# Schematic.net
KiCad netlist of a schematic drawn in EAGLE
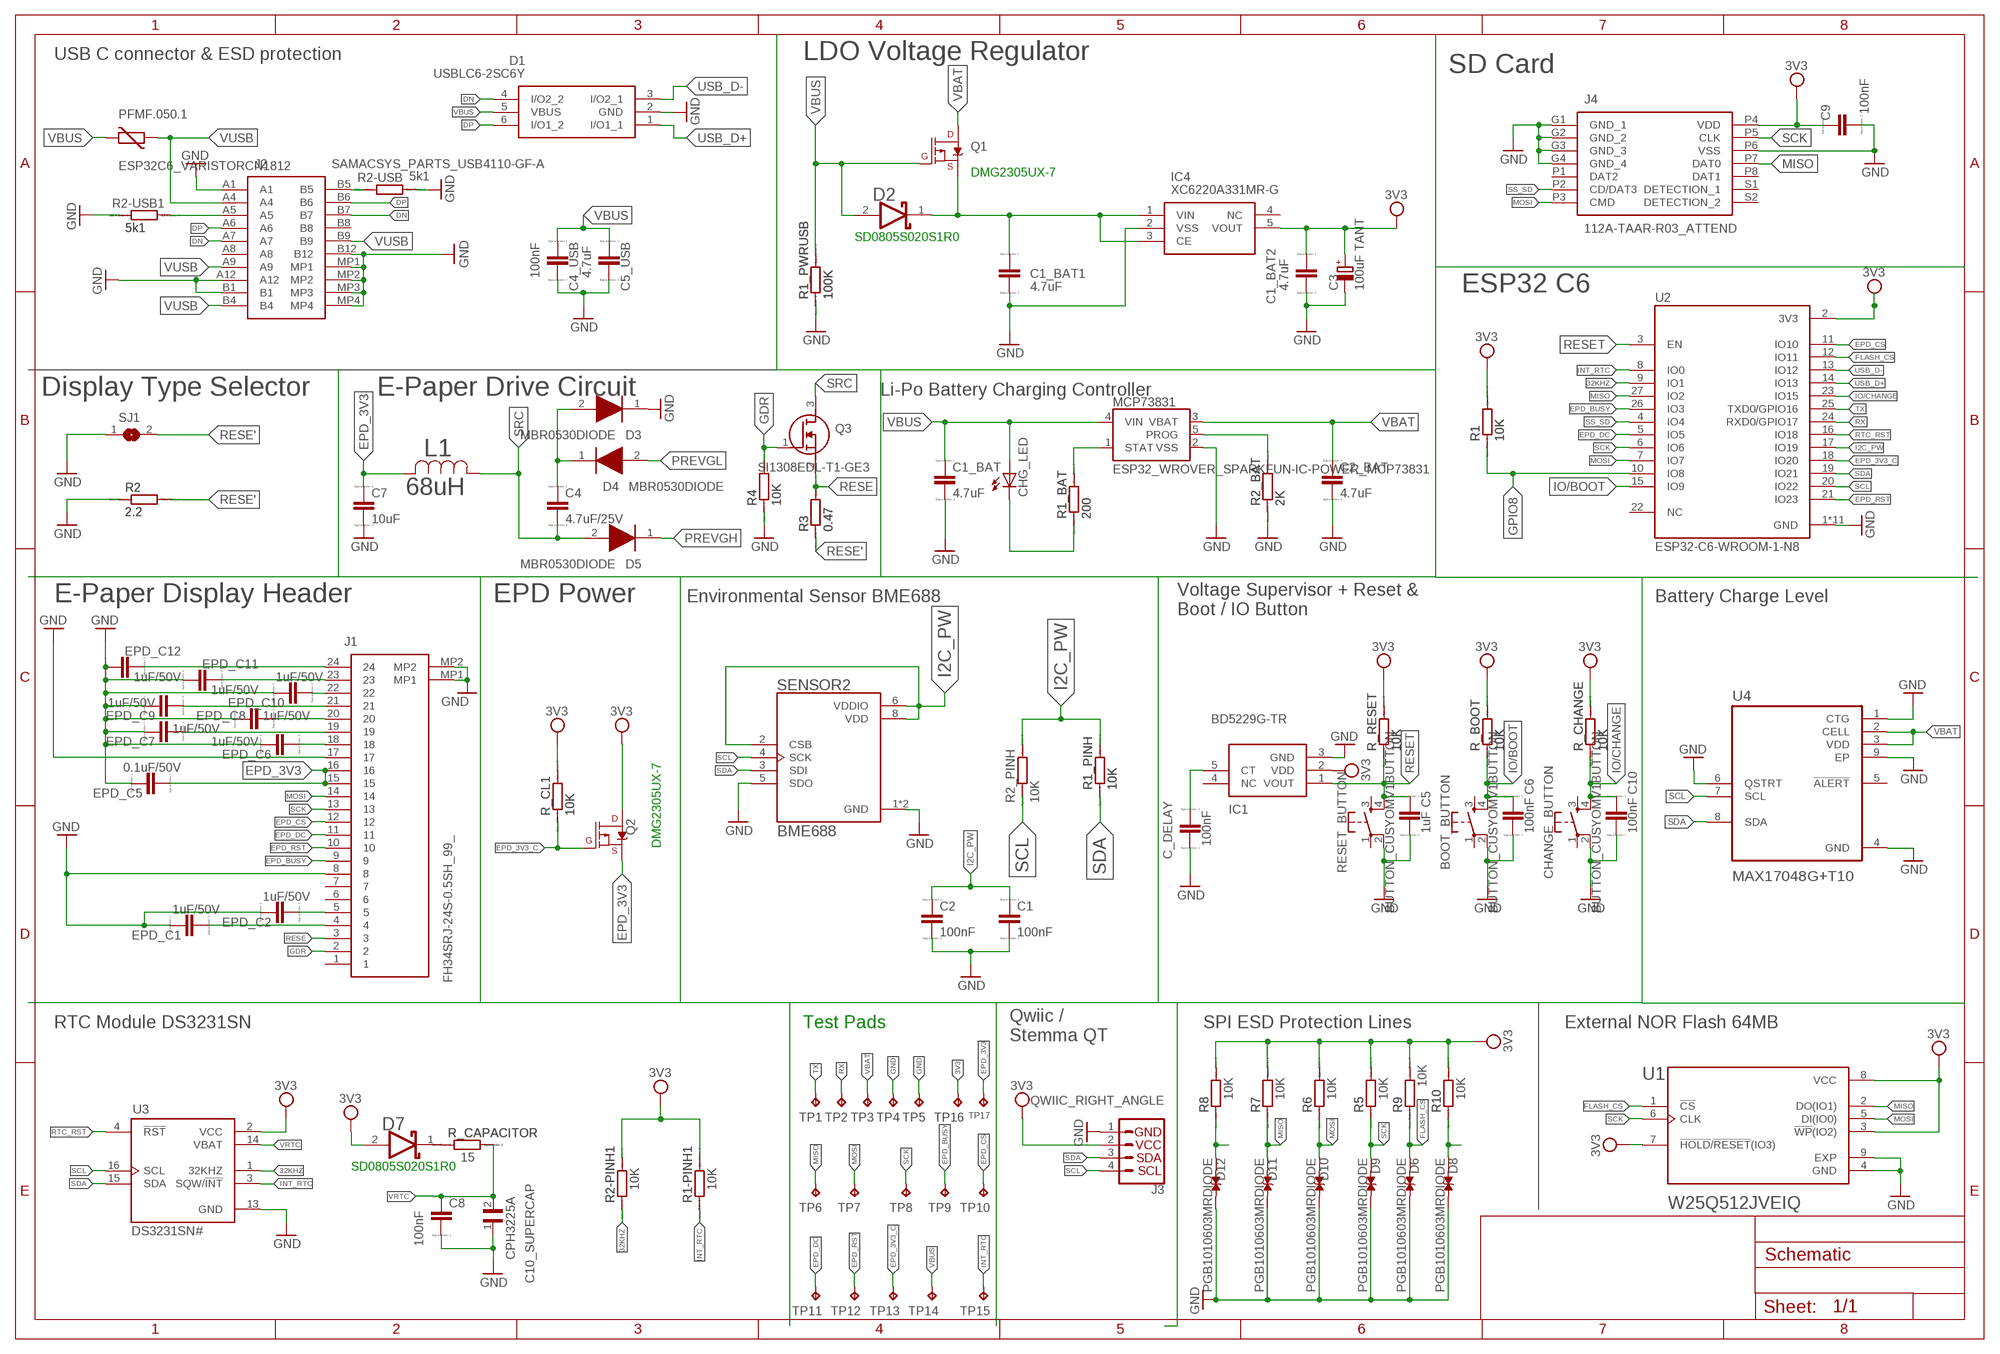
[diagram p0: schematic, sheet 1]

(export (version "E")
  (design (tool "Eeschema 10.0.6"))
  (components
    (comp (ref "BOOT_BUTTON")
      (value "BUTTON_CUSYOMV1BUTTON")
      (footprint "eagle-import:MYBUTTON")
      (libsource (lib "eagle-import") (part "BUTTON_CUSYOMV1BUTTON"))
    )
    (comp (ref "C1")
      (value "100nF")
      (footprint "eagle-import:EAGLE-LTSPICE_C0402")
      (libsource (lib "eagle-import") (part "ESP32_WROVER_EAGLE-LTSPICE_CC0402"))
    )
    (comp (ref "C1_BAT")
      (value "4.7uF")
      (footprint "eagle-import:EAGLE-LTSPICE_C0402")
      (libsource (lib "eagle-import") (part "ESP32_WROVER_EAGLE-LTSPICE_CC0402"))
    )
    (comp (ref "C1_BAT1")
      (value "4.7uF")
      (footprint "eagle-import:EAGLE-LTSPICE_C0402")
      (libsource (lib "eagle-import") (part "ESP32_WROVER_EAGLE-LTSPICE_CC0402"))
    )
    (comp (ref "C1_BAT2")
      (value "4.7uF")
      (footprint "eagle-import:EAGLE-LTSPICE_C0402")
      (libsource (lib "eagle-import") (part "ESP32_WROVER_EAGLE-LTSPICE_CC0402"))
    )
    (comp (ref "C2")
      (value "100nF")
      (footprint "eagle-import:EAGLE-LTSPICE_C0402")
      (libsource (lib "eagle-import") (part "ESP32_WROVER_EAGLE-LTSPICE_CC0402"))
    )
    (comp (ref "C2_BAT")
      (value "4.7uF")
      (footprint "eagle-import:EAGLE-LTSPICE_C0402")
      (libsource (lib "eagle-import") (part "ESP32_WROVER_EAGLE-LTSPICE_CC0402"))
    )
    (comp (ref "C3")
      (value "100uF TANT")
      (footprint "eagle-import:RCL_CT3528")
      (libsource (lib "eagle-import") (part "RCL_CPOL-EUCT3528"))
    )
    (comp (ref "C4")
      (value "4.7uF/25V")
      (footprint "eagle-import:EAGLE-LTSPICE_C0402")
      (libsource (lib "eagle-import") (part "ESP32_WROVER_EAGLE-LTSPICE_CC0402"))
    )
    (comp (ref "C4_USB")
      (value "100nF")
      (footprint "eagle-import:EAGLE-LTSPICE_C0402")
      (libsource (lib "eagle-import") (part "ESP32_WROVER_EAGLE-LTSPICE_CC0402"))
    )
    (comp (ref "C5")
      (value "1uF")
      (footprint "eagle-import:EAGLE-LTSPICE_C0402")
      (libsource (lib "eagle-import") (part "ESP32_WROVER_EAGLE-LTSPICE_CC0402"))
    )
    (comp (ref "C5_USB")
      (value "4.7uF")
      (footprint "eagle-import:EAGLE-LTSPICE_C0402")
      (libsource (lib "eagle-import") (part "ESP32_WROVER_EAGLE-LTSPICE_CC0402"))
    )
    (comp (ref "C6")
      (value "100nF")
      (footprint "eagle-import:EAGLE-LTSPICE_C0402")
      (libsource (lib "eagle-import") (part "ESP32_WROVER_EAGLE-LTSPICE_CC0402"))
    )
    (comp (ref "C7")
      (value "10uF")
      (footprint "eagle-import:EAGLE-LTSPICE_C0402")
      (libsource (lib "eagle-import") (part "ESP32_WROVER_EAGLE-LTSPICE_CC0402"))
    )
    (comp (ref "C8")
      (value "100nF")
      (footprint "eagle-import:EAGLE-LTSPICE_C0402")
      (libsource (lib "eagle-import") (part "ESP32_WROVER_EAGLE-LTSPICE_CC0402"))
    )
    (comp (ref "C9")
      (value "100nF")
      (footprint "eagle-import:EAGLE-LTSPICE_C0402")
      (libsource (lib "eagle-import") (part "ESP32_WROVER_EAGLE-LTSPICE_CC0402"))
    )
    (comp (ref "C10")
      (value "100nF")
      (footprint "eagle-import:EAGLE-LTSPICE_C0402")
      (libsource (lib "eagle-import") (part "ESP32_WROVER_EAGLE-LTSPICE_CC0402"))
    )
    (comp (ref "C10_SUPERCAP")
      (value "CPH3225A")
      (footprint "eagle-import:CAPCP3225X100N")
      (fields (field (name "MF") "Seiko Instruments"))
      (libsource (lib "eagle-import") (part "CPH3225A"))
    )
    (comp (ref "CHANGE_BUTTON")
      (value "BUTTON_CUSYOMV1BUTTON")
      (footprint "eagle-import:MYBUTTON")
      (libsource (lib "eagle-import") (part "BUTTON_CUSYOMV1BUTTON"))
    )
    (comp (ref "CHG_LED")
      (value "ADAFRUIT_LEDCHIP-LED0603")
      (footprint "eagle-import:ADAFRUIT_CHIP-LED0603")
      (libsource (lib "eagle-import") (part "ADAFRUIT_LEDCHIP-LED0603"))
    )
    (comp (ref "C_DELAY")
      (value "100nF")
      (footprint "eagle-import:EAGLE-LTSPICE_C0402")
      (libsource (lib "eagle-import") (part "ESP32_WROVER_EAGLE-LTSPICE_CC0402"))
    )
    (comp (ref "D1")
      (value "USBLC6-2SC6Y")
      (footprint "eagle-import:SOT95P280X145-6N")
      (fields (field (name "MF") "STMicroelectronics"))
      (libsource (lib "eagle-import") (part "USBLC6-2SC6Y"))
    )
    (comp (ref "D2")
      (value "SD0805S020S1R0")
      (footprint "eagle-import:ESP32_WROVER_AVX---SD0805S020S1R0_AVX_SD0805S020S1R0_0")
      (fields
        (field (name "DIGIKEY_PART_NUMBER") "478-7800-1-ND")
        (field (name "MF") "AVX")
        (field (name "MOUSER_PART_NUMBER") "581-SD0805S020S1R0")
      )
      (libsource (lib "eagle-import") (part "ESP32_WROVER_AVX---SD0805S020S1R0_AVX_SD0805S020S1R0_0_0AVX_SD0805S020S1R0_0_0"))
    )
    (comp (ref "D3")
      (value "MBR0530DIODE")
      (footprint "eagle-import:SOD3716X135N")
      (libsource (lib "eagle-import") (part "MBR0530DIODE"))
    )
    (comp (ref "D4")
      (value "MBR0530DIODE")
      (footprint "eagle-import:SOD3716X135N")
      (libsource (lib "eagle-import") (part "MBR0530DIODE"))
    )
    (comp (ref "D5")
      (value "MBR0530DIODE")
      (footprint "eagle-import:SOD3716X135N")
      (libsource (lib "eagle-import") (part "MBR0530DIODE"))
    )
    (comp (ref "D6")
      (value "PGB1010603MRDIODE")
      (footprint "eagle-import:DIOC1608X36N")
      (libsource (lib "eagle-import") (part "PGB1010603MRDIODE"))
    )
    (comp (ref "D7")
      (value "SD0805S020S1R0")
      (footprint "eagle-import:ESP32_WROVER_AVX---SD0805S020S1R0_AVX_SD0805S020S1R0_0")
      (fields
        (field (name "DIGIKEY_PART_NUMBER") "478-7800-1-ND")
        (field (name "MF") "AVX")
        (field (name "MOUSER_PART_NUMBER") "581-SD0805S020S1R0")
      )
      (libsource (lib "eagle-import") (part "ESP32_WROVER_AVX---SD0805S020S1R0_AVX_SD0805S020S1R0_0_0AVX_SD0805S020S1R0_0_0"))
    )
    (comp (ref "D8")
      (value "PGB1010603MRDIODE")
      (footprint "eagle-import:DIOC1608X36N")
      (libsource (lib "eagle-import") (part "PGB1010603MRDIODE"))
    )
    (comp (ref "D9")
      (value "PGB1010603MRDIODE")
      (footprint "eagle-import:DIOC1608X36N")
      (libsource (lib "eagle-import") (part "PGB1010603MRDIODE"))
    )
    (comp (ref "D10")
      (value "PGB1010603MRDIODE")
      (footprint "eagle-import:DIOC1608X36N")
      (libsource (lib "eagle-import") (part "PGB1010603MRDIODE"))
    )
    (comp (ref "D11")
      (value "PGB1010603MRDIODE")
      (footprint "eagle-import:DIOC1608X36N")
      (libsource (lib "eagle-import") (part "PGB1010603MRDIODE"))
    )
    (comp (ref "D12")
      (value "PGB1010603MRDIODE")
      (footprint "eagle-import:DIOC1608X36N")
      (libsource (lib "eagle-import") (part "PGB1010603MRDIODE"))
    )
    (comp (ref "EPD_C1")
      (value "1uF/50V")
      (footprint "eagle-import:EAGLE-LTSPICE_C0402")
      (libsource (lib "eagle-import") (part "ESP32_WROVER_EAGLE-LTSPICE_CC0402"))
    )
    (comp (ref "EPD_C2")
      (value "1uF/50V")
      (footprint "eagle-import:EAGLE-LTSPICE_C0402")
      (libsource (lib "eagle-import") (part "ESP32_WROVER_EAGLE-LTSPICE_CC0402"))
    )
    (comp (ref "EPD_C5")
      (value "0.1uF/50V")
      (footprint "eagle-import:EAGLE-LTSPICE_C0402")
      (libsource (lib "eagle-import") (part "ESP32_WROVER_EAGLE-LTSPICE_CC0402"))
    )
    (comp (ref "EPD_C6")
      (value "1uF/50V")
      (footprint "eagle-import:EAGLE-LTSPICE_C0402")
      (libsource (lib "eagle-import") (part "ESP32_WROVER_EAGLE-LTSPICE_CC0402"))
    )
    (comp (ref "EPD_C7")
      (value "1uF/50V")
      (footprint "eagle-import:EAGLE-LTSPICE_C0402")
      (libsource (lib "eagle-import") (part "ESP32_WROVER_EAGLE-LTSPICE_CC0402"))
    )
    (comp (ref "EPD_C8")
      (value "1uF/50V")
      (footprint "eagle-import:EAGLE-LTSPICE_C0402")
      (libsource (lib "eagle-import") (part "ESP32_WROVER_EAGLE-LTSPICE_CC0402"))
    )
    (comp (ref "EPD_C9")
      (value "1uF/50V")
      (footprint "eagle-import:EAGLE-LTSPICE_C0402")
      (libsource (lib "eagle-import") (part "ESP32_WROVER_EAGLE-LTSPICE_CC0402"))
    )
    (comp (ref "EPD_C10")
      (value "1uF/50V")
      (footprint "eagle-import:EAGLE-LTSPICE_C0402")
      (libsource (lib "eagle-import") (part "ESP32_WROVER_EAGLE-LTSPICE_CC0402"))
    )
    (comp (ref "EPD_C11")
      (value "1uF/50V")
      (footprint "eagle-import:EAGLE-LTSPICE_C0402")
      (libsource (lib "eagle-import") (part "ESP32_WROVER_EAGLE-LTSPICE_CC0402"))
    )
    (comp (ref "EPD_C12")
      (value "1uF/50V")
      (footprint "eagle-import:EAGLE-LTSPICE_C0402")
      (libsource (lib "eagle-import") (part "ESP32_WROVER_EAGLE-LTSPICE_CC0402"))
    )
    (comp (ref "IC1")
      (value "BD5229G-TR")
      (footprint "eagle-import:SOT95P280X125-5N")
      (fields (field (name "MOUSER_PART_NUMBER") "755-BD5229G-TR"))
      (libsource (lib "eagle-import") (part "BD5229G-TR"))
    )
    (comp (ref "IC4")
      (value "XC6220A331MR-G")
      (footprint "eagle-import:SOT95P280X120-5N")
      (fields (field (name "MOUSER_PART_NUMBER") "865-XC6220A331MR-G"))
      (libsource (lib "eagle-import") (part "XC6220A331MR-G"))
    )
    (comp (ref "J1")
      (value "FH34SRJ-24S-0.5SH_99_")
      (footprint "eagle-import:FH34SRJ24S05SH99")
      (fields
        (field (name "MANUFACTURER_PART_NUMBER") "FH34SRJ-24S-0.5SH(99)")
        (field (name "MOUSER_PART_NUMBER") "798-FH34SRJ24S05SH99")
      )
      (libsource (lib "eagle-import") (part "FH34SRJ-24S-0.5SH_99_"))
    )
    (comp (ref "J2")
      (value "SAMACSYS_PARTS_USB4110-GF-A")
      (footprint "eagle-import:SAMACSYS_PARTS_USB4110GFA")
      (fields
        (field (name "MANUFACTURER_PART_NUMBER") "USB4110-GF-A")
        (field (name "MOUSER_PART_NUMBER") "640-USB4110-GF-A")
      )
      (libsource (lib "eagle-import") (part "SAMACSYS_PARTS_USB4110-GF-A"))
    )
    (comp (ref "J3")
      (value "QWIIC_RIGHT_ANGLE")
      (footprint "eagle-import:JST04_1MM_RA")
      (libsource (lib "eagle-import") (part "QWIIC_CONNECTORJS-1MM"))
    )
    (comp (ref "J4")
      (value "112A-TAAR-R03_ATTEND")
      (footprint "eagle-import:112ATAARR03ATTEND")
      (fields (field (name "MANUFACTURER_PART_NUMBER") "112A-TAAR-R03 ATTEND"))
      (libsource (lib "eagle-import") (part "112A-TAAR-R03_ATTEND"))
    )
    (comp (ref "L1")
      (value "68uH")
      (footprint "eagle-import:IND_4828-WE-TPC_WRE")
      (fields
        (field (name "MANUFACTURER_PART_NUMBER") "744043680")
        (field (name "COPYRIGHT") "Copyright (C) 2024 Ultra Librarian. All rights reserved.")
      )
      (libsource (lib "eagle-import") (part "744043680IND_4828-WE-TPC_WRE"))
    )
    (comp (ref "MCP73831")
      (value "ESP32_WROVER_SPARKFUN-IC-POWER_MCP73831")
      (footprint "eagle-import:ESP32_WROVER_SPARKFUN-IC-POWER_SOT23-5")
      (libsource (lib "eagle-import") (part "ESP32_WROVER_SPARKFUN-IC-POWER_MCP73831"))
    )
    (comp (ref "PFMF.050.1")
      (value "ESP32C6_VARISTORCN1812")
      (footprint "eagle-import:ESP32C6_VARISTOR_CT_CN1812")
      (libsource (lib "eagle-import") (part "ESP32C6_VARISTORCN1812"))
    )
    (comp (ref "Q1")
      (value "20V/4.2A/52mΩ/1.4W")
      (footprint "eagle-import:ESP32_WROVER_SPARKFUN-DISCRETESEMI_SOT23-3")
      (libsource (lib "eagle-import") (part "ESP32_WROVER_SPARKFUN-DISCRETESEMI_MOSFET_PCH-DMG2305UX-7"))
    )
    (comp (ref "Q2")
      (value "20V/4.2A/52mΩ/1.4W")
      (footprint "eagle-import:ESP32_WROVER_SPARKFUN-DISCRETESEMI_SOT23-3")
      (libsource (lib "eagle-import") (part "ESP32_WROVER_SPARKFUN-DISCRETESEMI_MOSFET_PCH-DMG2305UX-7"))
    )
    (comp (ref "Q3")
      (value "SI1308EDL-T1-GE3")
      (footprint "eagle-import:SOT65P210X110-3N")
      (fields (field (name "MF") "Vishay Siliconix"))
      (libsource (lib "eagle-import") (part "SI1308EDL-T1-GE3"))
    )
    (comp (ref "R1")
      (value "10K")
      (footprint "eagle-import:ESP32_WROVER_EAGLE-LTSPICE_R0402")
      (libsource (lib "eagle-import") (part "ESP32_WROVER_EAGLE-LTSPICE_RR0402"))
    )
    (comp (ref "R1-PINH1")
      (value "10K")
      (footprint "eagle-import:ESP32_WROVER_EAGLE-LTSPICE_R0402")
      (libsource (lib "eagle-import") (part "ESP32_WROVER_EAGLE-LTSPICE_RR0402"))
    )
    (comp (ref "R1_BAT")
      (value "200")
      (footprint "eagle-import:ESP32_WROVER_EAGLE-LTSPICE_R0402")
      (libsource (lib "eagle-import") (part "ESP32_WROVER_EAGLE-LTSPICE_RR0402"))
    )
    (comp (ref "R1_PINH")
      (value "10K")
      (footprint "eagle-import:ESP32_WROVER_EAGLE-LTSPICE_R0402")
      (libsource (lib "eagle-import") (part "ESP32_WROVER_EAGLE-LTSPICE_RR0402"))
    )
    (comp (ref "R1_PWRUSB")
      (value "100K")
      (footprint "eagle-import:ESP32_WROVER_EAGLE-LTSPICE_R0402")
      (libsource (lib "eagle-import") (part "ESP32_WROVER_EAGLE-LTSPICE_RR0402"))
    )
    (comp (ref "R2")
      (value "2.2")
      (footprint "eagle-import:ESP32_WROVER_EAGLE-LTSPICE_R0402")
      (libsource (lib "eagle-import") (part "ESP32_WROVER_EAGLE-LTSPICE_RR0402"))
    )
    (comp (ref "R2-PINH1")
      (value "10K")
      (footprint "eagle-import:ESP32_WROVER_EAGLE-LTSPICE_R0402")
      (libsource (lib "eagle-import") (part "ESP32_WROVER_EAGLE-LTSPICE_RR0402"))
    )
    (comp (ref "R2-USB")
      (value "5k1")
      (footprint "eagle-import:ESP32_WROVER_EAGLE-LTSPICE_R0402")
      (libsource (lib "eagle-import") (part "ESP32_WROVER_EAGLE-LTSPICE_RR0402"))
    )
    (comp (ref "R2-USB1")
      (value "5k1")
      (footprint "eagle-import:ESP32_WROVER_EAGLE-LTSPICE_R0402")
      (libsource (lib "eagle-import") (part "ESP32_WROVER_EAGLE-LTSPICE_RR0402"))
    )
    (comp (ref "R2_BAT")
      (value "2K")
      (footprint "eagle-import:ESP32_WROVER_EAGLE-LTSPICE_R0402")
      (libsource (lib "eagle-import") (part "ESP32_WROVER_EAGLE-LTSPICE_RR0402"))
    )
    (comp (ref "R2_PINH")
      (value "10K")
      (footprint "eagle-import:ESP32_WROVER_EAGLE-LTSPICE_R0402")
      (libsource (lib "eagle-import") (part "ESP32_WROVER_EAGLE-LTSPICE_RR0402"))
    )
    (comp (ref "R3")
      (value "0.47")
      (footprint "eagle-import:ESP32_WROVER_EAGLE-LTSPICE_R0402")
      (libsource (lib "eagle-import") (part "ESP32_WROVER_EAGLE-LTSPICE_RR0402"))
    )
    (comp (ref "R4")
      (value "10K")
      (footprint "eagle-import:ESP32_WROVER_EAGLE-LTSPICE_R0402")
      (libsource (lib "eagle-import") (part "ESP32_WROVER_EAGLE-LTSPICE_RR0402"))
    )
    (comp (ref "R5")
      (value "10K")
      (footprint "eagle-import:ESP32_WROVER_EAGLE-LTSPICE_R0402")
      (libsource (lib "eagle-import") (part "ESP32_WROVER_EAGLE-LTSPICE_RR0402"))
    )
    (comp (ref "R6")
      (value "10K")
      (footprint "eagle-import:ESP32_WROVER_EAGLE-LTSPICE_R0402")
      (libsource (lib "eagle-import") (part "ESP32_WROVER_EAGLE-LTSPICE_RR0402"))
    )
    (comp (ref "R7")
      (value "10K")
      (footprint "eagle-import:ESP32_WROVER_EAGLE-LTSPICE_R0402")
      (libsource (lib "eagle-import") (part "ESP32_WROVER_EAGLE-LTSPICE_RR0402"))
    )
    (comp (ref "R8")
      (value "10K")
      (footprint "eagle-import:ESP32_WROVER_EAGLE-LTSPICE_R0402")
      (libsource (lib "eagle-import") (part "ESP32_WROVER_EAGLE-LTSPICE_RR0402"))
    )
    (comp (ref "R9")
      (value "10K")
      (footprint "eagle-import:ESP32_WROVER_EAGLE-LTSPICE_R0402")
      (libsource (lib "eagle-import") (part "ESP32_WROVER_EAGLE-LTSPICE_RR0402"))
    )
    (comp (ref "R10")
      (value "10K")
      (footprint "eagle-import:ESP32_WROVER_EAGLE-LTSPICE_R0402")
      (libsource (lib "eagle-import") (part "ESP32_WROVER_EAGLE-LTSPICE_RR0402"))
    )
    (comp (ref "RESET_BUTTON")
      (value "BUTTON_CUSYOMV1BUTTON")
      (footprint "eagle-import:MYBUTTON")
      (libsource (lib "eagle-import") (part "BUTTON_CUSYOMV1BUTTON"))
    )
    (comp (ref "R_BOOT")
      (value "10K")
      (footprint "eagle-import:ESP32_WROVER_EAGLE-LTSPICE_R0402")
      (libsource (lib "eagle-import") (part "ESP32_WROVER_EAGLE-LTSPICE_RR0402"))
    )
    (comp (ref "R_CAPACITOR")
      (value "15")
      (footprint "eagle-import:ESP32_WROVER_EAGLE-LTSPICE_R0402")
      (libsource (lib "eagle-import") (part "ESP32_WROVER_EAGLE-LTSPICE_RR0402"))
    )
    (comp (ref "R_CHANGE")
      (value "10K")
      (footprint "eagle-import:ESP32_WROVER_EAGLE-LTSPICE_R0402")
      (libsource (lib "eagle-import") (part "ESP32_WROVER_EAGLE-LTSPICE_RR0402"))
    )
    (comp (ref "R_CL1")
      (value "10K")
      (footprint "eagle-import:ESP32_WROVER_EAGLE-LTSPICE_R0402")
      (libsource (lib "eagle-import") (part "ESP32_WROVER_EAGLE-LTSPICE_RR0402"))
    )
    (comp (ref "R_RESET")
      (value "10K")
      (footprint "eagle-import:ESP32_WROVER_EAGLE-LTSPICE_R0402")
      (libsource (lib "eagle-import") (part "ESP32_WROVER_EAGLE-LTSPICE_RR0402"))
    )
    (comp (ref "SENSOR2")
      (value "BME688")
      (footprint "eagle-import:ESP32_WROVER_BME680_PSON80P300X300X100-8N")
      (fields (field (name "MF") "Bosch Sensortec") (field (name "MP") "BME680"))
      (libsource (lib "eagle-import") (part "ESP32_WROVER_BME680_BME680"))
    )
    (comp (ref "SJ1") (value "SJ") (footprint "eagle-import:SJ") (libsource (lib "eagle-import") (part "SJ")))
    (comp (ref "TP1")
      (value "TPTP20R")
      (footprint "eagle-import:TP20R")
      (libsource (lib "eagle-import") (part "TPTP20R"))
    )
    (comp (ref "TP2")
      (value "TPTP20R")
      (footprint "eagle-import:TP20R")
      (libsource (lib "eagle-import") (part "TPTP20R"))
    )
    (comp (ref "TP3")
      (value "TPTP20R")
      (footprint "eagle-import:TP20R")
      (libsource (lib "eagle-import") (part "TPTP20R"))
    )
    (comp (ref "TP4")
      (value "TPTP20R")
      (footprint "eagle-import:TP20R")
      (libsource (lib "eagle-import") (part "TPTP20R"))
    )
    (comp (ref "TP5")
      (value "TPTP20R")
      (footprint "eagle-import:TP20R")
      (libsource (lib "eagle-import") (part "TPTP20R"))
    )
    (comp (ref "TP6")
      (value "TPTP20R")
      (footprint "eagle-import:TP20R")
      (libsource (lib "eagle-import") (part "TPTP20R"))
    )
    (comp (ref "TP7")
      (value "TPTP20R")
      (footprint "eagle-import:TP20R")
      (libsource (lib "eagle-import") (part "TPTP20R"))
    )
    (comp (ref "TP8")
      (value "TPTP20R")
      (footprint "eagle-import:TP20R")
      (libsource (lib "eagle-import") (part "TPTP20R"))
    )
    (comp (ref "TP9")
      (value "TPTP20R")
      (footprint "eagle-import:TP20R")
      (libsource (lib "eagle-import") (part "TPTP20R"))
    )
    (comp (ref "TP10")
      (value "TPTP20R")
      (footprint "eagle-import:TP20R")
      (libsource (lib "eagle-import") (part "TPTP20R"))
    )
    (comp (ref "TP11")
      (value "TPTP20R")
      (footprint "eagle-import:TP20R")
      (libsource (lib "eagle-import") (part "TPTP20R"))
    )
    (comp (ref "TP12")
      (value "TPTP20R")
      (footprint "eagle-import:TP20R")
      (libsource (lib "eagle-import") (part "TPTP20R"))
    )
    (comp (ref "TP13")
      (value "TPTP20R")
      (footprint "eagle-import:TP20R")
      (libsource (lib "eagle-import") (part "TPTP20R"))
    )
    (comp (ref "TP14")
      (value "TPTP20R")
      (footprint "eagle-import:TP20R")
      (libsource (lib "eagle-import") (part "TPTP20R"))
    )
    (comp (ref "TP15")
      (value "TPTP20R")
      (footprint "eagle-import:TP20R")
      (libsource (lib "eagle-import") (part "TPTP20R"))
    )
    (comp (ref "TP16")
      (value "TPTP20R")
      (footprint "eagle-import:TP20R")
      (libsource (lib "eagle-import") (part "TPTP20R"))
    )
    (comp (ref "TP17")
      (value "TPTP20R")
      (footprint "eagle-import:TP20R")
      (libsource (lib "eagle-import") (part "TPTP20R"))
    )
    (comp (ref "U1")
      (value "W25Q512JVEIQ")
      (footprint "eagle-import:SON127P600X800X80-9N")
      (fields (field (name "MF") "Winbond Electronics"))
      (libsource (lib "eagle-import") (part "W25Q512JVEIQ"))
    )
    (comp (ref "U2")
      (value "ESP32-C6-WROOM-1-N8")
      (footprint "eagle-import:XCVR_ESP32-C6-WROOM-1-N8")
      (fields (field (name "MF") "Espressif Systems"))
      (libsource (lib "eagle-import") (part "ESP32-C6-WROOM-1-N8"))
    )
    (comp (ref "U3")
      (value "DS3231SN#")
      (footprint "eagle-import:SOIC127P1032X265-16N")
      (fields (field (name "MF") "Analog Devices"))
      (libsource (lib "eagle-import") (part "DS3231SN#"))
    )
    (comp (ref "U4")
      (value "MAX17048G+T10")
      (footprint "eagle-import:SON50P200X200X80-9N")
      (fields (field (name "MF") "Analog Devices"))
      (libsource (lib "eagle-import") (part "MAX17048G+T10"))
    )
  )
  (nets
    (net (code "1") (name "3V3") (class "Default")
      (node (ref "C1_BAT2") (pin "1") (pinfunction "1_1") (pintype "passive"))
      (node (ref "C3") (pin "+") (pinfunction "+_+") (pintype "passive"))
      (node (ref "C9") (pin "1") (pinfunction "1_1") (pintype "passive"))
      (node (ref "D7") (pin "2") (pinfunction "ANODE_2") (pintype "bidirectional"))
      (node (ref "IC1") (pin "2") (pinfunction "VDD_2") (pintype "bidirectional"))
      (node (ref "IC4") (pin "5") (pinfunction "VOUT_5") (pintype "bidirectional"))
      (node (ref "J3") (pin "2") (pinfunction "2_2") (pintype "power_in"))
      (node (ref "J4") (pin "P4") (pinfunction "VDD_P4") (pintype "bidirectional"))
      (node (ref "Q2") (pin "3") (pinfunction "D_3") (pintype "bidirectional"))
      (node (ref "R1") (pin "2") (pinfunction "2_2") (pintype "passive"))
      (node (ref "R1-PINH1") (pin "2") (pinfunction "2_2") (pintype "passive"))
      (node (ref "R10") (pin "2") (pinfunction "2_2") (pintype "passive"))
      (node (ref "R2-PINH1") (pin "2") (pinfunction "2_2") (pintype "passive"))
      (node (ref "R5") (pin "2") (pinfunction "2_2") (pintype "passive"))
      (node (ref "R6") (pin "2") (pinfunction "2_2") (pintype "passive"))
      (node (ref "R7") (pin "2") (pinfunction "2_2") (pintype "passive"))
      (node (ref "R8") (pin "2") (pinfunction "2_2") (pintype "passive"))
      (node (ref "R9") (pin "2") (pinfunction "2_2") (pintype "passive"))
      (node (ref "R_BOOT") (pin "2") (pinfunction "2_2") (pintype "passive"))
      (node (ref "R_CHANGE") (pin "2") (pinfunction "2_2") (pintype "passive"))
      (node (ref "R_CL1") (pin "2") (pinfunction "2_2") (pintype "passive"))
      (node (ref "R_RESET") (pin "2") (pinfunction "2_2") (pintype "passive"))
      (node (ref "TP16") (pin "TP") (pinfunction "TP_TP") (pintype "input"))
      (node (ref "U1") (pin "3") (pinfunction "~{WP}(IO2)_3") (pintype "bidirectional"))
      (node (ref "U1") (pin "7") (pinfunction "~{HOLD}/~{RESET}(IO3)_7") (pintype "bidirectional"))
      (node (ref "U1") (pin "8") (pinfunction "VCC_8") (pintype "power_in"))
      (node (ref "U2") (pin "2") (pinfunction "3V3_2") (pintype "power_in"))
      (node (ref "U3") (pin "2") (pinfunction "VCC_2") (pintype "power_in"))
    )
    (net (code "2") (name "32KHZ") (class "Default")
      (node (ref "R2-PINH1") (pin "1") (pinfunction "1_1") (pintype "passive"))
      (node (ref "U2") (pin "9") (pinfunction "IO1_9") (pintype "bidirectional"))
      (node (ref "U3") (pin "1") (pinfunction "32KHZ_1") (pintype "output"))
    )
    (net (code "3") (name "DN") (class "Default")
      (node (ref "D1") (pin "4") (pinfunction "I/O2_2_4") (pintype "bidirectional"))
      (node (ref "J2") (pin "A7") (pinfunction "A7_A7") (pintype "bidirectional"))
      (node (ref "J2") (pin "B7") (pinfunction "B7_B7") (pintype "bidirectional"))
    )
    (net (code "4") (name "DP") (class "Default")
      (node (ref "D1") (pin "6") (pinfunction "I/O1_2_6") (pintype "bidirectional"))
      (node (ref "J2") (pin "A6") (pinfunction "A6_A6") (pintype "bidirectional"))
      (node (ref "J2") (pin "B6") (pinfunction "B6_B6") (pintype "bidirectional"))
    )
    (net (code "5") (name "EPD_3V3") (class "Default")
      (node (ref "C7") (pin "1") (pinfunction "1_1") (pintype "passive"))
      (node (ref "EPD_C5") (pin "2") (pinfunction "2_2") (pintype "passive"))
      (node (ref "J1") (pin "15") (pinfunction "15_15") (pintype "bidirectional"))
      (node (ref "J1") (pin "16") (pinfunction "16_16") (pintype "bidirectional"))
      (node (ref "L1") (pin "2") (pinfunction "2_2") (pintype "passive"))
      (node (ref "Q2") (pin "2") (pinfunction "S_2") (pintype "bidirectional"))
      (node (ref "TP17") (pin "TP") (pinfunction "TP_TP") (pintype "input"))
    )
    (net (code "6") (name "EPD_3V3_C") (class "Default")
      (node (ref "Q2") (pin "1") (pinfunction "G_1") (pintype "bidirectional"))
      (node (ref "R_CL1") (pin "1") (pinfunction "1_1") (pintype "passive"))
      (node (ref "TP13") (pin "TP") (pinfunction "TP_TP") (pintype "input"))
      (node (ref "U2") (pin "18") (pinfunction "IO20_18") (pintype "bidirectional"))
    )
    (net (code "7") (name "EPD_BUSY") (class "Default")
      (node (ref "J1") (pin "9") (pinfunction "9_9") (pintype "bidirectional"))
      (node (ref "TP9") (pin "TP") (pinfunction "TP_TP") (pintype "input"))
      (node (ref "U2") (pin "26") (pinfunction "IO3_26") (pintype "bidirectional"))
    )
    (net (code "8") (name "EPD_CS") (class "Default")
      (node (ref "J1") (pin "12") (pinfunction "12_12") (pintype "bidirectional"))
      (node (ref "TP10") (pin "TP") (pinfunction "TP_TP") (pintype "input"))
      (node (ref "U2") (pin "11") (pinfunction "IO10_11") (pintype "bidirectional"))
    )
    (net (code "9") (name "EPD_DC") (class "Default")
      (node (ref "J1") (pin "11") (pinfunction "11_11") (pintype "bidirectional"))
      (node (ref "TP11") (pin "TP") (pinfunction "TP_TP") (pintype "input"))
      (node (ref "U2") (pin "5") (pinfunction "IO5_5") (pintype "bidirectional"))
    )
    (net (code "10") (name "EPD_RST") (class "Default")
      (node (ref "J1") (pin "10") (pinfunction "10_10") (pintype "bidirectional"))
      (node (ref "TP12") (pin "TP") (pinfunction "TP_TP") (pintype "input"))
      (node (ref "U2") (pin "21") (pinfunction "IO23_21") (pintype "bidirectional"))
    )
    (net (code "11") (name "FLASH_CS") (class "Default")
      (node (ref "D6") (pin "1") (pinfunction "1_1") (pintype "passive"))
      (node (ref "R9") (pin "1") (pinfunction "1_1") (pintype "passive"))
      (node (ref "U1") (pin "1") (pinfunction "~{CS}_1") (pintype "input"))
      (node (ref "U2") (pin "12") (pinfunction "IO11_12") (pintype "bidirectional"))
    )
    (net (code "12") (name "GDR") (class "Default")
      (node (ref "J1") (pin "2") (pinfunction "2_2") (pintype "bidirectional"))
      (node (ref "Q3") (pin "1") (pinfunction "G_1") (pintype "bidirectional"))
      (node (ref "R4") (pin "2") (pinfunction "2_2") (pintype "passive"))
    )
    (net (code "13") (name "GND") (class "Default")
      (node (ref "BOOT_BUTTON") (pin "2") (pinfunction "2_2") (pintype "passive"))
      (node (ref "C1") (pin "2") (pinfunction "2_2") (pintype "passive"))
      (node (ref "C10") (pin "2") (pinfunction "2_2") (pintype "passive"))
      (node (ref "C10_SUPERCAP") (pin "1") (pinfunction "1_1") (pintype "passive"))
      (node (ref "C1_BAT") (pin "2") (pinfunction "2_2") (pintype "passive"))
      (node (ref "C1_BAT1") (pin "2") (pinfunction "2_2") (pintype "passive"))
      (node (ref "C1_BAT2") (pin "2") (pinfunction "2_2") (pintype "passive"))
      (node (ref "C2") (pin "2") (pinfunction "2_2") (pintype "passive"))
      (node (ref "C2_BAT") (pin "2") (pinfunction "2_2") (pintype "passive"))
      (node (ref "C3") (pin "-") (pinfunction "-_-") (pintype "passive"))
      (node (ref "C4_USB") (pin "2") (pinfunction "2_2") (pintype "passive"))
      (node (ref "C5") (pin "2") (pinfunction "2_2") (pintype "passive"))
      (node (ref "C5_USB") (pin "2") (pinfunction "2_2") (pintype "passive"))
      (node (ref "C6") (pin "2") (pinfunction "2_2") (pintype "passive"))
      (node (ref "C7") (pin "2") (pinfunction "2_2") (pintype "passive"))
      (node (ref "C8") (pin "2") (pinfunction "2_2") (pintype "passive"))
      (node (ref "C9") (pin "2") (pinfunction "2_2") (pintype "passive"))
      (node (ref "CHANGE_BUTTON") (pin "2") (pinfunction "2_2") (pintype "passive"))
      (node (ref "C_DELAY") (pin "2") (pinfunction "2_2") (pintype "passive"))
      (node (ref "D1") (pin "2") (pinfunction "GND_2") (pintype "bidirectional"))
      (node (ref "D10") (pin "2") (pinfunction "2_2") (pintype "passive"))
      (node (ref "D11") (pin "2") (pinfunction "2_2") (pintype "passive"))
      (node (ref "D12") (pin "2") (pinfunction "2_2") (pintype "passive"))
      (node (ref "D3") (pin "1") (pinfunction "K_1") (pintype "bidirectional"))
      (node (ref "D6") (pin "2") (pinfunction "2_2") (pintype "passive"))
      (node (ref "D8") (pin "2") (pinfunction "2_2") (pintype "passive"))
      (node (ref "D9") (pin "2") (pinfunction "2_2") (pintype "passive"))
      (node (ref "EPD_C1") (pin "1") (pinfunction "1_1") (pintype "passive"))
      (node (ref "EPD_C10") (pin "1") (pinfunction "1_1") (pintype "passive"))
      (node (ref "EPD_C11") (pin "1") (pinfunction "1_1") (pintype "passive"))
      (node (ref "EPD_C12") (pin "1") (pinfunction "1_1") (pintype "passive"))
      (node (ref "EPD_C2") (pin "1") (pinfunction "1_1") (pintype "passive"))
      (node (ref "EPD_C5") (pin "1") (pinfunction "1_1") (pintype "passive"))
      (node (ref "EPD_C6") (pin "1") (pinfunction "1_1") (pintype "passive"))
      (node (ref "EPD_C7") (pin "1") (pinfunction "1_1") (pintype "passive"))
      (node (ref "EPD_C8") (pin "1") (pinfunction "1_1") (pintype "passive"))
      (node (ref "EPD_C9") (pin "1") (pinfunction "1_1") (pintype "passive"))
      (node (ref "IC1") (pin "3") (pinfunction "GND_3") (pintype "bidirectional"))
      (node (ref "IC4") (pin "2") (pinfunction "VSS_2") (pintype "bidirectional"))
      (node (ref "J1") (pin "17") (pinfunction "17_17") (pintype "bidirectional"))
      (node (ref "J1") (pin "8") (pinfunction "8_8") (pintype "bidirectional"))
      (node (ref "J1") (pin "MP1") (pinfunction "MP1_MP1") (pintype "bidirectional"))
      (node (ref "J1") (pin "MP2") (pinfunction "MP2_MP2") (pintype "bidirectional"))
      (node (ref "J2") (pin "A1") (pinfunction "A1_A1") (pintype "bidirectional"))
      (node (ref "J2") (pin "A12") (pinfunction "A12_A12") (pintype "bidirectional"))
      (node (ref "J2") (pin "B1") (pinfunction "B1_B1") (pintype "bidirectional"))
      (node (ref "J2") (pin "B12") (pinfunction "B12_B12") (pintype "bidirectional"))
      (node (ref "J2") (pin "MP1") (pinfunction "MP1_MP1") (pintype "bidirectional"))
      (node (ref "J2") (pin "MP2") (pinfunction "MP2_MP2") (pintype "bidirectional"))
      (node (ref "J2") (pin "MP3") (pinfunction "MP3_MP3") (pintype "bidirectional"))
      (node (ref "J2") (pin "MP4") (pinfunction "MP4_MP4") (pintype "bidirectional"))
      (node (ref "J3") (pin "1") (pinfunction "1_1") (pintype "power_in"))
      (node (ref "J4") (pin "G1") (pinfunction "GND_1_G1") (pintype "bidirectional"))
      (node (ref "J4") (pin "G2") (pinfunction "GND_2_G2") (pintype "bidirectional"))
      (node (ref "J4") (pin "G3") (pinfunction "GND_3_G3") (pintype "bidirectional"))
      (node (ref "J4") (pin "G4") (pinfunction "GND_4_G4") (pintype "bidirectional"))
      (node (ref "J4") (pin "P6") (pinfunction "VSS_P6") (pintype "bidirectional"))
      (node (ref "MCP73831") (pin "2") (pinfunction "VSS_2") (pintype "power_in"))
      (node (ref "R1_PWRUSB") (pin "1") (pinfunction "1_1") (pintype "passive"))
      (node (ref "R2") (pin "1") (pinfunction "1_1") (pintype "passive"))
      (node (ref "R2-USB") (pin "2") (pinfunction "2_2") (pintype "passive"))
      (node (ref "R2-USB1") (pin "1") (pinfunction "1_1") (pintype "passive"))
      (node (ref "R2_BAT") (pin "1") (pinfunction "1_1") (pintype "passive"))
      (node (ref "R4") (pin "1") (pinfunction "1_1") (pintype "passive"))
      (node (ref "RESET_BUTTON") (pin "2") (pinfunction "2_2") (pintype "passive"))
      (node (ref "SENSOR2") (pin "1") (pinfunction "GND_1") (pintype "power_in"))
      (node (ref "SENSOR2") (pin "5") (pinfunction "SDO_5") (pintype "bidirectional"))
      (node (ref "SENSOR2") (pin "7") (pinfunction "GND_7") (pintype "power_in"))
      (node (ref "SJ1") (pin "1") (pinfunction "1_1") (pintype "passive"))
      (node (ref "TP4") (pin "TP") (pinfunction "TP_TP") (pintype "input"))
      (node (ref "TP5") (pin "TP") (pinfunction "TP_TP") (pintype "input"))
      (node (ref "U1") (pin "4") (pinfunction "GND_4") (pintype "power_in"))
      (node (ref "U1") (pin "9") (pinfunction "EXP_9") (pintype "passive"))
      (node (ref "U2") (pin "1") (pinfunction "GND_1") (pintype "power_in"))
      (node (ref "U2") (pin "28") (pinfunction "GND_28") (pintype "power_in"))
      (node (ref "U2") (pin "29_1") (pinfunction "GND_29_1") (pintype "power_in"))
      (node (ref "U2") (pin "29_2") (pinfunction "GND_29_2") (pintype "power_in"))
      (node (ref "U2") (pin "29_3") (pinfunction "GND_29_3") (pintype "power_in"))
      (node (ref "U2") (pin "29_4") (pinfunction "GND_29_4") (pintype "power_in"))
      (node (ref "U2") (pin "29_5") (pinfunction "GND_29_5") (pintype "power_in"))
      (node (ref "U2") (pin "29_6") (pinfunction "GND_29_6") (pintype "power_in"))
      (node (ref "U2") (pin "29_7") (pinfunction "GND_29_7") (pintype "power_in"))
      (node (ref "U2") (pin "29_8") (pinfunction "GND_29_8") (pintype "power_in"))
      (node (ref "U2") (pin "29_9") (pinfunction "GND_29_9") (pintype "power_in"))
      (node (ref "U3") (pin "13") (pinfunction "GND_13") (pintype "power_in"))
      (node (ref "U4") (pin "1") (pinfunction "CTG_1") (pintype "power_in"))
      (node (ref "U4") (pin "4") (pinfunction "GND_4") (pintype "power_in"))
      (node (ref "U4") (pin "6") (pinfunction "QSTRT_6") (pintype "input"))
      (node (ref "U4") (pin "9") (pinfunction "EP_9") (pintype "power_in"))
    )
    (net (code "14") (name "GPIO8") (class "Default")
      (node (ref "R1") (pin "1") (pinfunction "1_1") (pintype "passive"))
      (node (ref "U2") (pin "10") (pinfunction "IO8_10") (pintype "bidirectional"))
    )
    (net (code "15") (name "I2C_PW") (class "Default")
      (node (ref "C1") (pin "1") (pinfunction "1_1") (pintype "passive"))
      (node (ref "C2") (pin "1") (pinfunction "1_1") (pintype "passive"))
      (node (ref "R1_PINH") (pin "2") (pinfunction "2_2") (pintype "passive"))
      (node (ref "R2_PINH") (pin "2") (pinfunction "2_2") (pintype "passive"))
      (node (ref "SENSOR2") (pin "2") (pinfunction "CSB_2") (pintype "input"))
      (node (ref "SENSOR2") (pin "6") (pinfunction "VDDIO_6") (pintype "power_in"))
      (node (ref "SENSOR2") (pin "8") (pinfunction "VDD_8") (pintype "power_in"))
      (node (ref "U2") (pin "17") (pinfunction "IO19_17") (pintype "bidirectional"))
    )
    (net (code "16") (name "INT_RTC") (class "Default")
      (node (ref "R1-PINH1") (pin "1") (pinfunction "1_1") (pintype "passive"))
      (node (ref "TP15") (pin "TP") (pinfunction "TP_TP") (pintype "input"))
      (node (ref "U2") (pin "8") (pinfunction "IO0_8") (pintype "bidirectional"))
      (node (ref "U3") (pin "3") (pinfunction "SQW/~{INT}_3") (pintype "output"))
    )
    (net (code "17") (name "IO{slash}BOOT") (class "Default")
      (node (ref "BOOT_BUTTON") (pin "4") (pinfunction "4_4") (pintype "passive"))
      (node (ref "C6") (pin "1") (pinfunction "1_1") (pintype "passive"))
      (node (ref "R_BOOT") (pin "1") (pinfunction "1_1") (pintype "passive"))
      (node (ref "U2") (pin "15") (pinfunction "IO9_15") (pintype "bidirectional"))
    )
    (net (code "18") (name "IO{slash}CHANGE") (class "Default")
      (node (ref "C10") (pin "1") (pinfunction "1_1") (pintype "passive"))
      (node (ref "CHANGE_BUTTON") (pin "4") (pinfunction "4_4") (pintype "passive"))
      (node (ref "R_CHANGE") (pin "1") (pinfunction "1_1") (pintype "passive"))
      (node (ref "U2") (pin "23") (pinfunction "IO15_23") (pintype "bidirectional"))
    )
    (net (code "19") (name "MISO") (class "Default")
      (node (ref "D11") (pin "1") (pinfunction "1_1") (pintype "passive"))
      (node (ref "J4") (pin "P7") (pinfunction "DAT0_P7") (pintype "bidirectional"))
      (node (ref "R7") (pin "1") (pinfunction "1_1") (pintype "passive"))
      (node (ref "TP6") (pin "TP") (pinfunction "TP_TP") (pintype "input"))
      (node (ref "U1") (pin "2") (pinfunction "DO(IO1)_2") (pintype "bidirectional"))
      (node (ref "U2") (pin "27") (pinfunction "IO2_27") (pintype "bidirectional"))
    )
    (net (code "20") (name "MOSI") (class "Default")
      (node (ref "D10") (pin "1") (pinfunction "1_1") (pintype "passive"))
      (node (ref "J1") (pin "14") (pinfunction "14_14") (pintype "bidirectional"))
      (node (ref "J4") (pin "P3") (pinfunction "CMD_P3") (pintype "bidirectional"))
      (node (ref "R6") (pin "1") (pinfunction "1_1") (pintype "passive"))
      (node (ref "TP7") (pin "TP") (pinfunction "TP_TP") (pintype "input"))
      (node (ref "U1") (pin "5") (pinfunction "DI(IO0)_5") (pintype "bidirectional"))
      (node (ref "U2") (pin "7") (pinfunction "IO7_7") (pintype "bidirectional"))
    )
    (net (code "21") (name "Net-(CHG_LED-PadC)") (class "Default")
      (node (ref "CHG_LED") (pin "C") (pinfunction "C_C") (pintype "passive"))
      (node (ref "R1_BAT") (pin "1") (pinfunction "1_1") (pintype "passive"))
    )
    (net (code "22") (name "Net-(D2-CATHODE)") (class "Default")
      (node (ref "C1_BAT1") (pin "1") (pinfunction "1_1") (pintype "passive"))
      (node (ref "D2") (pin "1") (pinfunction "CATHODE_1") (pintype "bidirectional"))
      (node (ref "IC4") (pin "1") (pinfunction "VIN_1") (pintype "bidirectional"))
      (node (ref "IC4") (pin "3") (pinfunction "CE_3") (pintype "bidirectional"))
      (node (ref "Q1") (pin "2") (pinfunction "S_2") (pintype "bidirectional"))
    )
    (net (code "23") (name "Net-(D3-A)") (class "Default")
      (node (ref "C4") (pin "1") (pinfunction "1_1") (pintype "passive"))
      (node (ref "D3") (pin "2") (pinfunction "A_2") (pintype "bidirectional"))
      (node (ref "D4") (pin "1") (pinfunction "K_1") (pintype "bidirectional"))
    )
    (net (code "24") (name "Net-(D7-CATHODE)") (class "Default")
      (node (ref "D7") (pin "1") (pinfunction "CATHODE_1") (pintype "bidirectional"))
      (node (ref "R_CAPACITOR") (pin "1") (pinfunction "1_1") (pintype "passive"))
    )
    (net (code "25") (name "Net-(D8-Pad1)") (class "Default")
      (node (ref "D8") (pin "1") (pinfunction "1_1") (pintype "passive"))
      (node (ref "R10") (pin "1") (pinfunction "1_1") (pintype "passive"))
    )
    (net (code "26") (name "Net-(D12-Pad1)") (class "Default")
      (node (ref "D12") (pin "1") (pinfunction "1_1") (pintype "passive"))
      (node (ref "R8") (pin "1") (pinfunction "1_1") (pintype "passive"))
    )
    (net (code "27") (name "Net-(EPD_C1-Pad2)") (class "Default")
      (node (ref "EPD_C1") (pin "2") (pinfunction "2_2") (pintype "passive"))
      (node (ref "J1") (pin "4") (pinfunction "4_4") (pintype "bidirectional"))
    )
    (net (code "28") (name "Net-(EPD_C2-Pad2)") (class "Default")
      (node (ref "EPD_C2") (pin "2") (pinfunction "2_2") (pintype "passive"))
      (node (ref "J1") (pin "5") (pinfunction "5_5") (pintype "bidirectional"))
    )
    (net (code "29") (name "Net-(EPD_C6-Pad2)") (class "Default")
      (node (ref "EPD_C6") (pin "2") (pinfunction "2_2") (pintype "passive"))
      (node (ref "J1") (pin "18") (pinfunction "18_18") (pintype "bidirectional"))
    )
    (net (code "30") (name "Net-(EPD_C7-Pad2)") (class "Default")
      (node (ref "EPD_C7") (pin "2") (pinfunction "2_2") (pintype "passive"))
      (node (ref "J1") (pin "19") (pinfunction "19_19") (pintype "bidirectional"))
    )
    (net (code "31") (name "Net-(EPD_C8-Pad2)") (class "Default")
      (node (ref "EPD_C8") (pin "2") (pinfunction "2_2") (pintype "passive"))
      (node (ref "J1") (pin "20") (pinfunction "20_20") (pintype "bidirectional"))
    )
    (net (code "32") (name "Net-(EPD_C9-Pad2)") (class "Default")
      (node (ref "EPD_C9") (pin "2") (pinfunction "2_2") (pintype "passive"))
      (node (ref "J1") (pin "21") (pinfunction "21_21") (pintype "bidirectional"))
    )
    (net (code "33") (name "Net-(EPD_C10-Pad2)") (class "Default")
      (node (ref "EPD_C10") (pin "2") (pinfunction "2_2") (pintype "passive"))
      (node (ref "J1") (pin "22") (pinfunction "22_22") (pintype "bidirectional"))
    )
    (net (code "34") (name "Net-(EPD_C11-Pad2)") (class "Default")
      (node (ref "EPD_C11") (pin "2") (pinfunction "2_2") (pintype "passive"))
      (node (ref "J1") (pin "23") (pinfunction "23_23") (pintype "bidirectional"))
    )
    (net (code "35") (name "Net-(EPD_C12-Pad2)") (class "Default")
      (node (ref "EPD_C12") (pin "2") (pinfunction "2_2") (pintype "passive"))
      (node (ref "J1") (pin "24") (pinfunction "24_24") (pintype "bidirectional"))
    )
    (net (code "36") (name "Net-(IC1-CT)") (class "Default")
      (node (ref "C_DELAY") (pin "1") (pinfunction "1_1") (pintype "passive"))
      (node (ref "IC1") (pin "5") (pinfunction "CT_5") (pintype "bidirectional"))
    )
    (net (code "37") (name "Net-(J2-PadA5)") (class "Default")
      (node (ref "J2") (pin "A5") (pinfunction "A5_A5") (pintype "bidirectional"))
      (node (ref "R2-USB1") (pin "2") (pinfunction "2_2") (pintype "passive"))
    )
    (net (code "38") (name "Net-(J2-PadB5)") (class "Default")
      (node (ref "J2") (pin "B5") (pinfunction "B5_B5") (pintype "bidirectional"))
      (node (ref "R2-USB") (pin "1") (pinfunction "1_1") (pintype "passive"))
    )
    (net (code "39") (name "Net-(MCP73831-PROG)") (class "Default")
      (node (ref "MCP73831") (pin "5") (pinfunction "PROG_5") (pintype "input"))
      (node (ref "R2_BAT") (pin "2") (pinfunction "2_2") (pintype "passive"))
    )
    (net (code "40") (name "Net-(MCP73831-STAT)") (class "Default")
      (node (ref "MCP73831") (pin "1") (pinfunction "STAT_1") (pintype "output"))
      (node (ref "R1_BAT") (pin "2") (pinfunction "2_2") (pintype "passive"))
    )
    (net (code "41") (name "PREVGH") (class "Default")
      (node (ref "D5") (pin "1") (pinfunction "K_1") (pintype "bidirectional"))
    )
    (net (code "42") (name "PREVGL") (class "Default")
      (node (ref "D4") (pin "2") (pinfunction "A_2") (pintype "bidirectional"))
    )
    (net (code "43") (name "RESE") (class "Default")
      (node (ref "J1") (pin "3") (pinfunction "3_3") (pintype "bidirectional"))
      (node (ref "Q3") (pin "2") (pinfunction "S_2") (pintype "bidirectional"))
      (node (ref "R3") (pin "2") (pinfunction "2_2") (pintype "passive"))
    )
    (net (code "44") (name "RESE'") (class "Default")
      (node (ref "R2") (pin "2") (pinfunction "2_2") (pintype "passive"))
      (node (ref "R3") (pin "1") (pinfunction "1_1") (pintype "passive"))
      (node (ref "SJ1") (pin "2") (pinfunction "2_2") (pintype "passive"))
    )
    (net (code "45") (name "RESET") (class "Default")
      (node (ref "C5") (pin "1") (pinfunction "1_1") (pintype "passive"))
      (node (ref "IC1") (pin "1") (pinfunction "VOUT_1") (pintype "bidirectional"))
      (node (ref "RESET_BUTTON") (pin "4") (pinfunction "4_4") (pintype "passive"))
      (node (ref "R_RESET") (pin "1") (pinfunction "1_1") (pintype "passive"))
      (node (ref "U2") (pin "3") (pinfunction "EN_3") (pintype "input"))
    )
    (net (code "46") (name "RTC_RST") (class "Default")
      (node (ref "U2") (pin "16") (pinfunction "IO18_16") (pintype "bidirectional"))
      (node (ref "U3") (pin "4") (pinfunction "~{RST}_4") (pintype "input"))
    )
    (net (code "47") (name "RX") (class "Default")
      (node (ref "TP2") (pin "TP") (pinfunction "TP_TP") (pintype "input"))
      (node (ref "U2") (pin "24") (pinfunction "RXD0/GPIO17_24") (pintype "bidirectional"))
    )
    (net (code "48") (name "SCK") (class "Default")
      (node (ref "D9") (pin "1") (pinfunction "1_1") (pintype "passive"))
      (node (ref "J1") (pin "13") (pinfunction "13_13") (pintype "bidirectional"))
      (node (ref "J4") (pin "P5") (pinfunction "CLK_P5") (pintype "bidirectional"))
      (node (ref "R5") (pin "1") (pinfunction "1_1") (pintype "passive"))
      (node (ref "TP8") (pin "TP") (pinfunction "TP_TP") (pintype "input"))
      (node (ref "U1") (pin "6") (pinfunction "CLK_6") (pintype "input"))
      (node (ref "U2") (pin "6") (pinfunction "IO6_6") (pintype "bidirectional"))
    )
    (net (code "49") (name "SCL") (class "Default")
      (node (ref "J3") (pin "4") (pinfunction "4_4") (pintype "passive"))
      (node (ref "R2_PINH") (pin "1") (pinfunction "1_1") (pintype "passive"))
      (node (ref "SENSOR2") (pin "4") (pinfunction "SCK_4") (pintype "input"))
      (node (ref "U2") (pin "20") (pinfunction "IO22_20") (pintype "bidirectional"))
      (node (ref "U3") (pin "16") (pinfunction "SCL_16") (pintype "input"))
      (node (ref "U4") (pin "7") (pinfunction "SCL_7") (pintype "input"))
    )
    (net (code "50") (name "SDA") (class "Default")
      (node (ref "J3") (pin "3") (pinfunction "3_3") (pintype "passive"))
      (node (ref "R1_PINH") (pin "1") (pinfunction "1_1") (pintype "passive"))
      (node (ref "SENSOR2") (pin "3") (pinfunction "SDI_3") (pintype "bidirectional"))
      (node (ref "U2") (pin "19") (pinfunction "IO21_19") (pintype "bidirectional"))
      (node (ref "U3") (pin "15") (pinfunction "SDA_15") (pintype "bidirectional"))
      (node (ref "U4") (pin "8") (pinfunction "SDA_8") (pintype "bidirectional"))
    )
    (net (code "51") (name "SRC") (class "Default")
      (node (ref "C4") (pin "2") (pinfunction "2_2") (pintype "passive"))
      (node (ref "D5") (pin "2") (pinfunction "A_2") (pintype "bidirectional"))
      (node (ref "L1") (pin "1") (pinfunction "1_1") (pintype "passive"))
      (node (ref "Q3") (pin "3") (pinfunction "D_3") (pintype "bidirectional"))
    )
    (net (code "52") (name "SS_SD") (class "Default")
      (node (ref "J4") (pin "P2") (pinfunction "CD/DAT3_P2") (pintype "bidirectional"))
      (node (ref "U2") (pin "4") (pinfunction "IO4_4") (pintype "bidirectional"))
    )
    (net (code "53") (name "TX") (class "Default")
      (node (ref "TP1") (pin "TP") (pinfunction "TP_TP") (pintype "input"))
      (node (ref "U2") (pin "25") (pinfunction "TXD0/GPIO16_25") (pintype "bidirectional"))
    )
    (net (code "54") (name "USB_D+") (class "Default")
      (node (ref "D1") (pin "1") (pinfunction "I/O1_1_1") (pintype "bidirectional"))
      (node (ref "U2") (pin "14") (pinfunction "IO13_14") (pintype "bidirectional"))
    )
    (net (code "55") (name "USB_D-") (class "Default")
      (node (ref "D1") (pin "3") (pinfunction "I/O2_1_3") (pintype "bidirectional"))
      (node (ref "U2") (pin "13") (pinfunction "IO12_13") (pintype "bidirectional"))
    )
    (net (code "56") (name "VBAT") (class "Default")
      (node (ref "C2_BAT") (pin "1") (pinfunction "1_1") (pintype "passive"))
      (node (ref "MCP73831") (pin "3") (pinfunction "VBAT_3") (pintype "power_in"))
      (node (ref "Q1") (pin "3") (pinfunction "D_3") (pintype "bidirectional"))
      (node (ref "TP3") (pin "TP") (pinfunction "TP_TP") (pintype "input"))
      (node (ref "U4") (pin "2") (pinfunction "CELL_2") (pintype "power_in"))
      (node (ref "U4") (pin "3") (pinfunction "VDD_3") (pintype "power_in"))
    )
    (net (code "57") (name "VBUS") (class "Default")
      (node (ref "C1_BAT") (pin "1") (pinfunction "1_1") (pintype "passive"))
      (node (ref "C4_USB") (pin "1") (pinfunction "1_1") (pintype "passive"))
      (node (ref "C5_USB") (pin "1") (pinfunction "1_1") (pintype "passive"))
      (node (ref "CHG_LED") (pin "A") (pinfunction "A_A") (pintype "passive"))
      (node (ref "D1") (pin "5") (pinfunction "VBUS_5") (pintype "bidirectional"))
      (node (ref "D2") (pin "2") (pinfunction "ANODE_2") (pintype "bidirectional"))
      (node (ref "MCP73831") (pin "4") (pinfunction "VIN_4") (pintype "power_in"))
      (node (ref "PFMF.050.1") (pin "2") (pinfunction "2_2") (pintype "passive"))
      (node (ref "Q1") (pin "1") (pinfunction "G_1") (pintype "bidirectional"))
      (node (ref "R1_PWRUSB") (pin "2") (pinfunction "2_2") (pintype "passive"))
      (node (ref "TP14") (pin "TP") (pinfunction "TP_TP") (pintype "input"))
    )
    (net (code "58") (name "VRTC") (class "Default")
      (node (ref "C10_SUPERCAP") (pin "2") (pinfunction "2_2") (pintype "passive"))
      (node (ref "C8") (pin "1") (pinfunction "1_1") (pintype "passive"))
      (node (ref "R_CAPACITOR") (pin "2") (pinfunction "2_2") (pintype "passive"))
      (node (ref "U3") (pin "14") (pinfunction "VBAT_14") (pintype "power_in"))
    )
    (net (code "59") (name "VUSB") (class "Default")
      (node (ref "J2") (pin "A4") (pinfunction "A4_A4") (pintype "bidirectional"))
      (node (ref "J2") (pin "A9") (pinfunction "A9_A9") (pintype "bidirectional"))
      (node (ref "J2") (pin "B4") (pinfunction "B4_B4") (pintype "bidirectional"))
      (node (ref "J2") (pin "B9") (pinfunction "B9_B9") (pintype "bidirectional"))
      (node (ref "PFMF.050.1") (pin "1") (pinfunction "1_1") (pintype "passive"))
    )
    (net (code "60") (name "unconnected-(BOOT_BUTTON-Pad1)") (class "Default")
      (node (ref "BOOT_BUTTON") (pin "1") (pinfunction "1_1") (pintype "passive"))
    )
    (net (code "61") (name "unconnected-(BOOT_BUTTON-Pad3)") (class "Default")
      (node (ref "BOOT_BUTTON") (pin "3") (pinfunction "3_3") (pintype "passive"))
    )
    (net (code "62") (name "unconnected-(CHANGE_BUTTON-Pad1)") (class "Default")
      (node (ref "CHANGE_BUTTON") (pin "1") (pinfunction "1_1") (pintype "passive"))
    )
    (net (code "63") (name "unconnected-(CHANGE_BUTTON-Pad3)") (class "Default")
      (node (ref "CHANGE_BUTTON") (pin "3") (pinfunction "3_3") (pintype "passive"))
    )
    (net (code "64") (name "unconnected-(IC1-NC-Pad4)") (class "Default")
      (node (ref "IC1") (pin "4") (pinfunction "NC_4") (pintype "no_connect"))
    )
    (net (code "65") (name "unconnected-(IC4-NC-Pad4)") (class "Default")
      (node (ref "IC4") (pin "4") (pinfunction "NC_4") (pintype "no_connect"))
    )
    (net (code "66") (name "unconnected-(J1-Pad1)") (class "Default")
      (node (ref "J1") (pin "1") (pinfunction "1_1") (pintype "bidirectional"))
    )
    (net (code "67") (name "unconnected-(J1-Pad6)") (class "Default")
      (node (ref "J1") (pin "6") (pinfunction "6_6") (pintype "bidirectional"))
    )
    (net (code "68") (name "unconnected-(J1-Pad7)") (class "Default")
      (node (ref "J1") (pin "7") (pinfunction "7_7") (pintype "bidirectional"))
    )
    (net (code "69") (name "unconnected-(J2-PadA8)") (class "Default")
      (node (ref "J2") (pin "A8") (pinfunction "A8_A8") (pintype "bidirectional"))
    )
    (net (code "70") (name "unconnected-(J2-PadB8)") (class "Default")
      (node (ref "J2") (pin "B8") (pinfunction "B8_B8") (pintype "bidirectional"))
    )
    (net (code "71") (name "unconnected-(J4-DAT1-PadP8)") (class "Default")
      (node (ref "J4") (pin "P8") (pinfunction "DAT1_P8") (pintype "bidirectional"))
    )
    (net (code "72") (name "unconnected-(J4-DAT2-PadP1)") (class "Default")
      (node (ref "J4") (pin "P1") (pinfunction "DAT2_P1") (pintype "bidirectional"))
    )
    (net (code "73") (name "unconnected-(J4-DETECTION_1-PadS1)") (class "Default")
      (node (ref "J4") (pin "S1") (pinfunction "DETECTION_1_S1") (pintype "bidirectional"))
    )
    (net (code "74") (name "unconnected-(J4-DETECTION_2-PadS2)") (class "Default")
      (node (ref "J4") (pin "S2") (pinfunction "DETECTION_2_S2") (pintype "bidirectional"))
    )
    (net (code "75") (name "unconnected-(RESET_BUTTON-Pad1)") (class "Default")
      (node (ref "RESET_BUTTON") (pin "1") (pinfunction "1_1") (pintype "passive"))
    )
    (net (code "76") (name "unconnected-(RESET_BUTTON-Pad3)") (class "Default")
      (node (ref "RESET_BUTTON") (pin "3") (pinfunction "3_3") (pintype "passive"))
    )
    (net (code "77") (name "unconnected-(U2-NC-Pad22)") (class "Default")
      (node (ref "U2") (pin "22") (pinfunction "NC_22") (pintype "no_connect"))
    )
    (net (code "78") (name "unconnected-(U4-~{ALERT}-Pad5)") (class "Default")
      (node (ref "U4") (pin "5") (pinfunction "~{ALERT}_5") (pintype "output"))
    )
  )
)
